# GNSS-proto.net
KiCad netlist of a schematic drawn in EAGLE
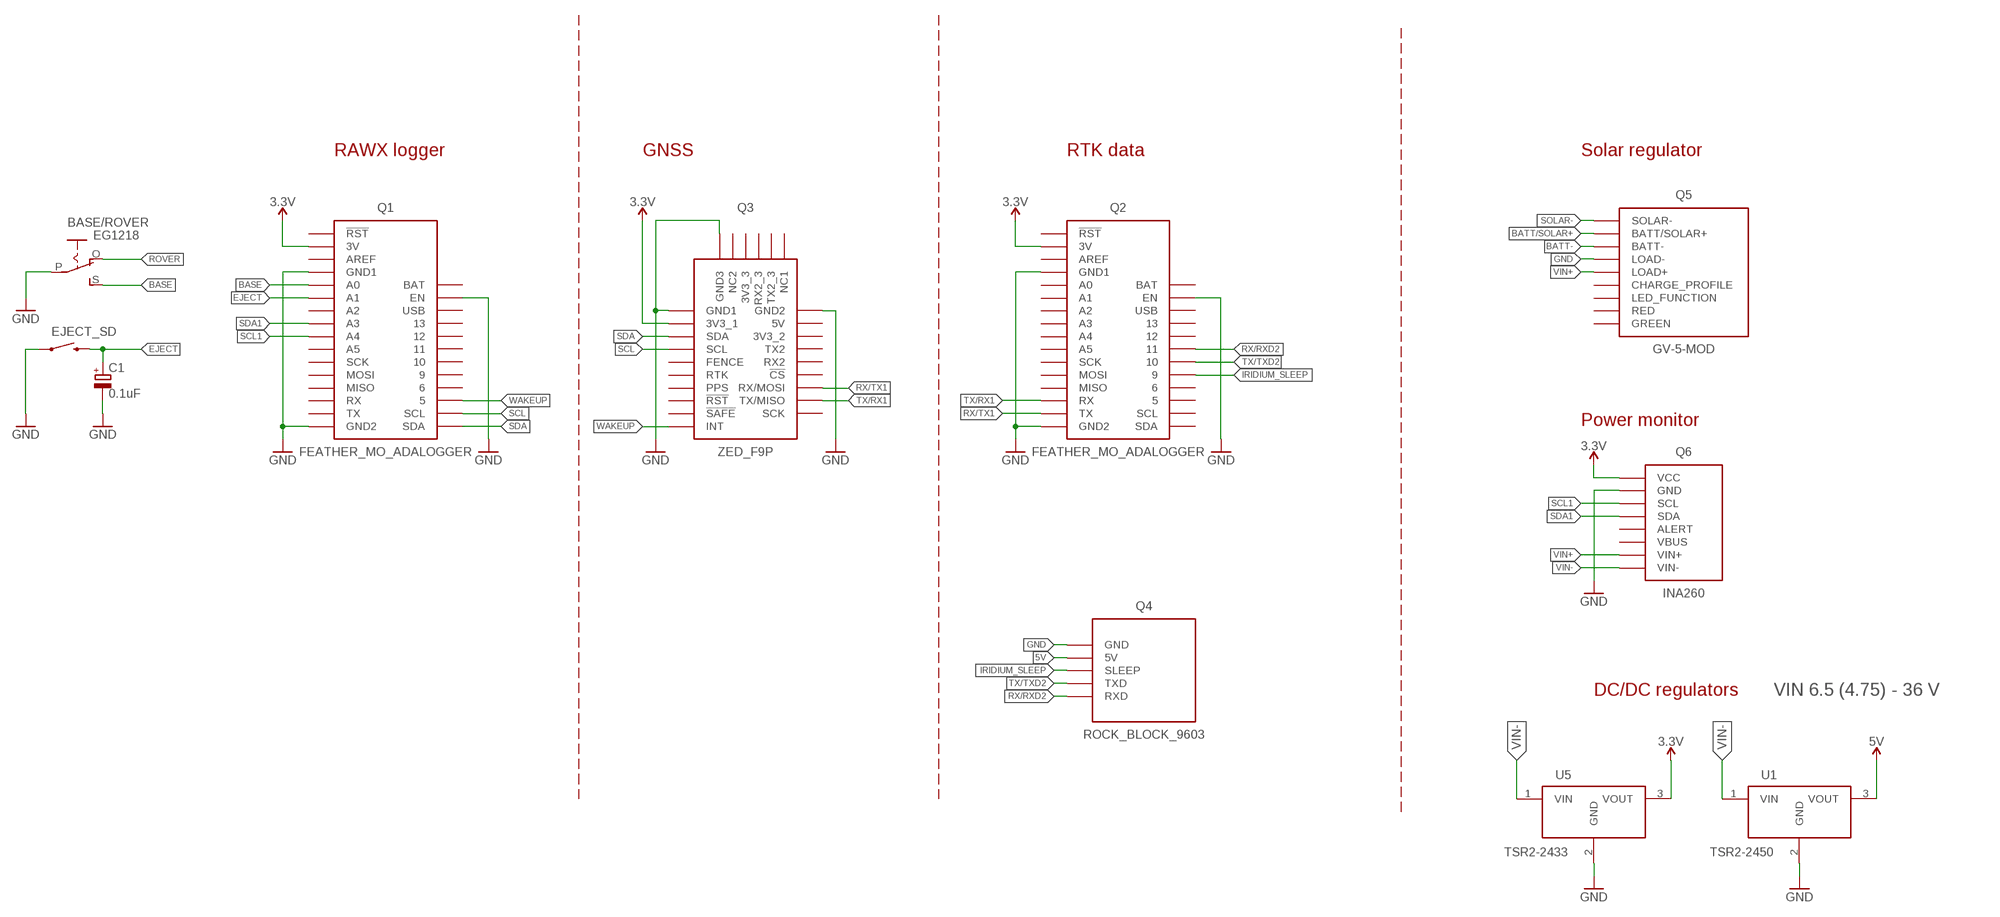
[diagram p0: schematic, sheet 1]

(export (version "E")
  (design (tool "Eeschema 10.0.6"))
  (components
    (comp (ref "BASE/ROVER")
      (value "EG1218")
      (footprint "eagle-import:EG1218")
      (libsource (lib "eagle-import") (part "EG1218S"))
    )
    (comp (ref "C1")
      (value "0.1uF")
      (footprint "eagle-import:E2,5-6E")
      (libsource (lib "eagle-import") (part "CPOL-EUE2,5-6E"))
    )
    (comp (ref "EJECT_SD")
      (value "SWITCH-MOMENTARY-2PTH")
      (footprint "eagle-import:TACTILE-PTH")
      (libsource (lib "eagle-import") (part "SWITCH-MOMENTARY-2PTH"))
    )
    (comp (ref "Q1")
      (value "FEATHER_MO_ADALOGGER")
      (footprint "eagle-import:FEATHER_M0_ADALOGGER")
      (libsource (lib "eagle-import") (part "FEATHER_MO_ADALOGGER"))
    )
    (comp (ref "Q2")
      (value "FEATHER_MO_ADALOGGER")
      (footprint "eagle-import:FEATHER_M0_ADALOGGER")
      (libsource (lib "eagle-import") (part "FEATHER_MO_ADALOGGER"))
    )
    (comp (ref "Q3")
      (value "ZED_F9P")
      (footprint "eagle-import:ZED_F9P")
      (libsource (lib "eagle-import") (part "ZED_F9P"))
    )
    (comp (ref "Q4")
      (value "ROCK_BLOCK_9603")
      (footprint "eagle-import:ROCK_BLOCK_9603")
      (libsource (lib "eagle-import") (part "ROCK_BLOCK_9603"))
    )
    (comp (ref "Q5")
      (value "GV-5-MOD")
      (footprint "eagle-import:GV-5-MOD")
      (libsource (lib "eagle-import") (part "GV-5-MOD"))
    )
    (comp (ref "Q6")
      (value "INA260")
      (footprint "eagle-import:INA260")
      (libsource (lib "eagle-import") (part "INA260"))
    )
    (comp (ref "U1")
      (value "TSR2-2450")
      (footprint "eagle-import:173010535")
      (fields
        (field (name "DIGIKEY_PARTNO") "732-173010535-ND")
        (field (name "MANUFACTURER") "Würth Elektronik")
        (field (name "MPN") "173010535")
        (field (name "CREATED_BY") "PCBLayout.com")
      )
      (libsource (lib "eagle-import") (part "173010535"))
    )
    (comp (ref "U5")
      (value "TSR2-2433")
      (footprint "eagle-import:173010535")
      (fields
        (field (name "DIGIKEY_PARTNO") "732-173010535-ND")
        (field (name "MANUFACTURER") "Würth Elektronik")
        (field (name "MPN") "173010535")
        (field (name "CREATED_BY") "PCBLayout.com")
      )
      (libsource (lib "eagle-import") (part "173010535"))
    )
  )
  (nets
    (net (code "1") (name "3.3V") (class "Default")
      (node (ref "Q1") (pin "3V") (pinfunction "3V_3V") (pintype "bidirectional"))
      (node (ref "Q2") (pin "3V") (pinfunction "3V_3V") (pintype "bidirectional"))
      (node (ref "Q3") (pin "3V3_1") (pinfunction "3V3_1_3V3_1") (pintype "bidirectional"))
      (node (ref "Q6") (pin "VCC") (pinfunction "VCC_VCC") (pintype "bidirectional"))
      (node (ref "U5") (pin "3") (pinfunction "VOUT_3") (pintype "power_in"))
    )
    (net (code "2") (name "5V") (class "Default")
      (node (ref "Q4") (pin "5V") (pinfunction "5V_5V") (pintype "bidirectional"))
      (node (ref "U1") (pin "3") (pinfunction "VOUT_3") (pintype "power_in"))
    )
    (net (code "3") (name "BASE") (class "Default")
      (node (ref "BASE/ROVER") (pin "S") (pinfunction "S_S") (pintype "passive"))
      (node (ref "Q1") (pin "A0") (pinfunction "A0_A0") (pintype "bidirectional"))
    )
    (net (code "4") (name "BATT-") (class "Default")
      (node (ref "Q5") (pin "BATT-1") (pinfunction "BATT-_BATT-1") (pintype "bidirectional"))
      (node (ref "Q5") (pin "BATT-2") (pinfunction "BATT-_BATT-2") (pintype "bidirectional"))
      (node (ref "Q5") (pin "BATT-3") (pinfunction "BATT-_BATT-3") (pintype "bidirectional"))
      (node (ref "Q5") (pin "BATT-4") (pinfunction "BATT-_BATT-4") (pintype "bidirectional"))
    )
    (net (code "5") (name "BATT{slash}SOLAR+") (class "Default")
      (node (ref "Q5") (pin "BATT/SOLAR+1") (pinfunction "BATT/SOLAR+_BATT/SOLAR+1") (pintype "bidirectional"))
      (node (ref "Q5") (pin "BATT/SOLAR+2") (pinfunction "BATT/SOLAR+_BATT/SOLAR+2") (pintype "bidirectional"))
      (node (ref "Q5") (pin "BATT/SOLAR+3") (pinfunction "BATT/SOLAR+_BATT/SOLAR+3") (pintype "bidirectional"))
      (node (ref "Q5") (pin "BATT/SOLAR+4") (pinfunction "BATT/SOLAR+_BATT/SOLAR+4") (pintype "bidirectional"))
    )
    (net (code "6") (name "EJECT") (class "Default")
      (node (ref "C1") (pin "+") (pinfunction "+_+") (pintype "passive"))
      (node (ref "EJECT_SD") (pin "3") (pinfunction "2_3") (pintype "passive"))
      (node (ref "Q1") (pin "A1") (pinfunction "A1_A1") (pintype "bidirectional"))
    )
    (net (code "7") (name "GND") (class "Default")
      (node (ref "BASE/ROVER") (pin "P") (pinfunction "P_P") (pintype "passive"))
      (node (ref "C1") (pin "-") (pinfunction "-_-") (pintype "passive"))
      (node (ref "EJECT_SD") (pin "1") (pinfunction "1_1") (pintype "passive"))
      (node (ref "Q1") (pin "EN") (pinfunction "EN_EN") (pintype "bidirectional"))
      (node (ref "Q1") (pin "GND1") (pinfunction "GND1_GND1") (pintype "bidirectional"))
      (node (ref "Q1") (pin "GND2") (pinfunction "GND2_GND2") (pintype "bidirectional"))
      (node (ref "Q2") (pin "EN") (pinfunction "EN_EN") (pintype "bidirectional"))
      (node (ref "Q2") (pin "GND1") (pinfunction "GND1_GND1") (pintype "bidirectional"))
      (node (ref "Q2") (pin "GND2") (pinfunction "GND2_GND2") (pintype "bidirectional"))
      (node (ref "Q3") (pin "GND1") (pinfunction "GND1_GND1") (pintype "bidirectional"))
      (node (ref "Q3") (pin "GND2") (pinfunction "GND2_GND2") (pintype "bidirectional"))
      (node (ref "Q3") (pin "GND3") (pinfunction "GND3_GND3") (pintype "bidirectional"))
      (node (ref "Q4") (pin "GND1") (pinfunction "GND_GND1") (pintype "bidirectional"))
      (node (ref "Q4") (pin "GND2") (pinfunction "GND_GND2") (pintype "bidirectional"))
      (node (ref "Q5") (pin "LOAD-1") (pinfunction "LOAD-_LOAD-1") (pintype "bidirectional"))
      (node (ref "Q5") (pin "LOAD-2") (pinfunction "LOAD-_LOAD-2") (pintype "bidirectional"))
      (node (ref "Q5") (pin "LOAD-3") (pinfunction "LOAD-_LOAD-3") (pintype "bidirectional"))
      (node (ref "Q5") (pin "LOAD-4") (pinfunction "LOAD-_LOAD-4") (pintype "bidirectional"))
      (node (ref "Q6") (pin "GND") (pinfunction "GND_GND") (pintype "bidirectional"))
      (node (ref "U1") (pin "2") (pinfunction "GND_2") (pintype "power_in"))
      (node (ref "U5") (pin "2") (pinfunction "GND_2") (pintype "power_in"))
    )
    (net (code "8") (name "IRIDIUM_SLEEP") (class "Default")
      (node (ref "Q2") (pin "9") (pinfunction "9_9") (pintype "bidirectional"))
      (node (ref "Q4") (pin "SLEEP") (pinfunction "SLEEP_SLEEP") (pintype "bidirectional"))
    )
    (net (code "9") (name "ROVER") (class "Default")
      (node (ref "BASE/ROVER") (pin "O") (pinfunction "O_O") (pintype "passive"))
    )
    (net (code "10") (name "RX{slash}RXD2") (class "Default")
      (node (ref "Q2") (pin "11") (pinfunction "11_11") (pintype "bidirectional"))
      (node (ref "Q4") (pin "RXD") (pinfunction "RXD_RXD") (pintype "bidirectional"))
    )
    (net (code "11") (name "RX{slash}TX1") (class "Default")
      (node (ref "Q2") (pin "TX") (pinfunction "TX_TX") (pintype "bidirectional"))
      (node (ref "Q3") (pin "RX/MOSI") (pinfunction "RX/MOSI_RX/MOSI") (pintype "bidirectional"))
    )
    (net (code "12") (name "SCL") (class "Default")
      (node (ref "Q1") (pin "SCL") (pinfunction "SCL_SCL") (pintype "bidirectional"))
      (node (ref "Q3") (pin "SCL") (pinfunction "SCL_SCL") (pintype "bidirectional"))
    )
    (net (code "13") (name "SCL1") (class "Default")
      (node (ref "Q1") (pin "A4") (pinfunction "A4_A4") (pintype "bidirectional"))
      (node (ref "Q6") (pin "SCL") (pinfunction "SCL_SCL") (pintype "bidirectional"))
    )
    (net (code "14") (name "SDA") (class "Default")
      (node (ref "Q1") (pin "SDA") (pinfunction "SDA_SDA") (pintype "bidirectional"))
      (node (ref "Q3") (pin "SDA") (pinfunction "SDA_SDA") (pintype "bidirectional"))
    )
    (net (code "15") (name "SDA1") (class "Default")
      (node (ref "Q1") (pin "A3") (pinfunction "A3_A3") (pintype "bidirectional"))
      (node (ref "Q6") (pin "SDA") (pinfunction "SDA_SDA") (pintype "bidirectional"))
    )
    (net (code "16") (name "SOLAR-") (class "Default")
      (node (ref "Q5") (pin "SOLAR-1") (pinfunction "SOLAR-_SOLAR-1") (pintype "bidirectional"))
      (node (ref "Q5") (pin "SOLAR-2") (pinfunction "SOLAR-_SOLAR-2") (pintype "bidirectional"))
      (node (ref "Q5") (pin "SOLAR-3") (pinfunction "SOLAR-_SOLAR-3") (pintype "bidirectional"))
      (node (ref "Q5") (pin "SOLAR-4") (pinfunction "SOLAR-_SOLAR-4") (pintype "bidirectional"))
    )
    (net (code "17") (name "TX{slash}RX1") (class "Default")
      (node (ref "Q2") (pin "RX") (pinfunction "RX_RX") (pintype "bidirectional"))
      (node (ref "Q3") (pin "TX/MISO") (pinfunction "TX/MISO_TX/MISO") (pintype "bidirectional"))
    )
    (net (code "18") (name "TX{slash}TXD2") (class "Default")
      (node (ref "Q2") (pin "10") (pinfunction "10_10") (pintype "bidirectional"))
      (node (ref "Q4") (pin "TXD") (pinfunction "TXD_TXD") (pintype "bidirectional"))
    )
    (net (code "19") (name "VIN+") (class "Default")
      (node (ref "Q5") (pin "LOAD+1") (pinfunction "LOAD+_LOAD+1") (pintype "bidirectional"))
      (node (ref "Q5") (pin "LOAD+2") (pinfunction "LOAD+_LOAD+2") (pintype "bidirectional"))
      (node (ref "Q5") (pin "LOAD+3") (pinfunction "LOAD+_LOAD+3") (pintype "bidirectional"))
      (node (ref "Q5") (pin "LOAD+4") (pinfunction "LOAD+_LOAD+4") (pintype "bidirectional"))
      (node (ref "Q6") (pin "VIN+1") (pinfunction "VIN+_VIN+1") (pintype "bidirectional"))
      (node (ref "Q6") (pin "VIN+2") (pinfunction "VIN+_VIN+2") (pintype "bidirectional"))
    )
    (net (code "20") (name "VIN-") (class "Default")
      (node (ref "Q6") (pin "VIN-1") (pinfunction "VIN-_VIN-1") (pintype "bidirectional"))
      (node (ref "Q6") (pin "VIN-2") (pinfunction "VIN-_VIN-2") (pintype "bidirectional"))
      (node (ref "U1") (pin "1") (pinfunction "VIN_1") (pintype "power_in"))
      (node (ref "U5") (pin "1") (pinfunction "VIN_1") (pintype "power_in"))
    )
    (net (code "21") (name "WAKEUP") (class "Default")
      (node (ref "Q1") (pin "5") (pinfunction "5_5") (pintype "bidirectional"))
      (node (ref "Q3") (pin "INT") (pinfunction "INT_INT") (pintype "bidirectional"))
    )
    (net (code "22") (name "unconnected-(Q1-Pad6)") (class "Default")
      (node (ref "Q1") (pin "6") (pinfunction "6_6") (pintype "bidirectional"))
    )
    (net (code "23") (name "unconnected-(Q1-Pad9)") (class "Default")
      (node (ref "Q1") (pin "9") (pinfunction "9_9") (pintype "bidirectional"))
    )
    (net (code "24") (name "unconnected-(Q1-Pad10)") (class "Default")
      (node (ref "Q1") (pin "10") (pinfunction "10_10") (pintype "bidirectional"))
    )
    (net (code "25") (name "unconnected-(Q1-Pad11)") (class "Default")
      (node (ref "Q1") (pin "11") (pinfunction "11_11") (pintype "bidirectional"))
    )
    (net (code "26") (name "unconnected-(Q1-Pad12)") (class "Default")
      (node (ref "Q1") (pin "12") (pinfunction "12_12") (pintype "bidirectional"))
    )
    (net (code "27") (name "unconnected-(Q1-Pad13)") (class "Default")
      (node (ref "Q1") (pin "13") (pinfunction "13_13") (pintype "bidirectional"))
    )
    (net (code "28") (name "unconnected-(Q1-PadA2)") (class "Default")
      (node (ref "Q1") (pin "A2") (pinfunction "A2_A2") (pintype "bidirectional"))
    )
    (net (code "29") (name "unconnected-(Q1-PadA5)") (class "Default")
      (node (ref "Q1") (pin "A5") (pinfunction "A5_A5") (pintype "bidirectional"))
    )
    (net (code "30") (name "unconnected-(Q1-PadAREF)") (class "Default")
      (node (ref "Q1") (pin "AREF") (pinfunction "AREF_AREF") (pintype "bidirectional"))
    )
    (net (code "31") (name "unconnected-(Q1-PadBAT)") (class "Default")
      (node (ref "Q1") (pin "BAT") (pinfunction "BAT_BAT") (pintype "bidirectional"))
    )
    (net (code "32") (name "unconnected-(Q1-PadMISO)") (class "Default")
      (node (ref "Q1") (pin "MISO") (pinfunction "MISO_MISO") (pintype "bidirectional"))
    )
    (net (code "33") (name "unconnected-(Q1-PadMOSI)") (class "Default")
      (node (ref "Q1") (pin "MOSI") (pinfunction "MOSI_MOSI") (pintype "bidirectional"))
    )
    (net (code "34") (name "unconnected-(Q1-PadRX)") (class "Default")
      (node (ref "Q1") (pin "RX") (pinfunction "RX_RX") (pintype "bidirectional"))
    )
    (net (code "35") (name "unconnected-(Q1-PadSCK)") (class "Default")
      (node (ref "Q1") (pin "SCK") (pinfunction "SCK_SCK") (pintype "bidirectional"))
    )
    (net (code "36") (name "unconnected-(Q1-PadTX)") (class "Default")
      (node (ref "Q1") (pin "TX") (pinfunction "TX_TX") (pintype "bidirectional"))
    )
    (net (code "37") (name "unconnected-(Q1-PadUSB)") (class "Default")
      (node (ref "Q1") (pin "USB") (pinfunction "USB_USB") (pintype "bidirectional"))
    )
    (net (code "38") (name "unconnected-(Q1-~{RST}-Pad!RST)") (class "Default")
      (node (ref "Q1") (pin "!RST") (pinfunction "~{RST}_!RST") (pintype "bidirectional"))
    )
    (net (code "39") (name "unconnected-(Q2-Pad5)") (class "Default")
      (node (ref "Q2") (pin "5") (pinfunction "5_5") (pintype "bidirectional"))
    )
    (net (code "40") (name "unconnected-(Q2-Pad6)") (class "Default")
      (node (ref "Q2") (pin "6") (pinfunction "6_6") (pintype "bidirectional"))
    )
    (net (code "41") (name "unconnected-(Q2-Pad12)") (class "Default")
      (node (ref "Q2") (pin "12") (pinfunction "12_12") (pintype "bidirectional"))
    )
    (net (code "42") (name "unconnected-(Q2-Pad13)") (class "Default")
      (node (ref "Q2") (pin "13") (pinfunction "13_13") (pintype "bidirectional"))
    )
    (net (code "43") (name "unconnected-(Q2-PadA0)") (class "Default")
      (node (ref "Q2") (pin "A0") (pinfunction "A0_A0") (pintype "bidirectional"))
    )
    (net (code "44") (name "unconnected-(Q2-PadA1)") (class "Default")
      (node (ref "Q2") (pin "A1") (pinfunction "A1_A1") (pintype "bidirectional"))
    )
    (net (code "45") (name "unconnected-(Q2-PadA2)") (class "Default")
      (node (ref "Q2") (pin "A2") (pinfunction "A2_A2") (pintype "bidirectional"))
    )
    (net (code "46") (name "unconnected-(Q2-PadA3)") (class "Default")
      (node (ref "Q2") (pin "A3") (pinfunction "A3_A3") (pintype "bidirectional"))
    )
    (net (code "47") (name "unconnected-(Q2-PadA4)") (class "Default")
      (node (ref "Q2") (pin "A4") (pinfunction "A4_A4") (pintype "bidirectional"))
    )
    (net (code "48") (name "unconnected-(Q2-PadA5)") (class "Default")
      (node (ref "Q2") (pin "A5") (pinfunction "A5_A5") (pintype "bidirectional"))
    )
    (net (code "49") (name "unconnected-(Q2-PadAREF)") (class "Default")
      (node (ref "Q2") (pin "AREF") (pinfunction "AREF_AREF") (pintype "bidirectional"))
    )
    (net (code "50") (name "unconnected-(Q2-PadBAT)") (class "Default")
      (node (ref "Q2") (pin "BAT") (pinfunction "BAT_BAT") (pintype "bidirectional"))
    )
    (net (code "51") (name "unconnected-(Q2-PadMISO)") (class "Default")
      (node (ref "Q2") (pin "MISO") (pinfunction "MISO_MISO") (pintype "bidirectional"))
    )
    (net (code "52") (name "unconnected-(Q2-PadMOSI)") (class "Default")
      (node (ref "Q2") (pin "MOSI") (pinfunction "MOSI_MOSI") (pintype "bidirectional"))
    )
    (net (code "53") (name "unconnected-(Q2-PadSCK)") (class "Default")
      (node (ref "Q2") (pin "SCK") (pinfunction "SCK_SCK") (pintype "bidirectional"))
    )
    (net (code "54") (name "unconnected-(Q2-PadSCL)") (class "Default")
      (node (ref "Q2") (pin "SCL") (pinfunction "SCL_SCL") (pintype "bidirectional"))
    )
    (net (code "55") (name "unconnected-(Q2-PadSDA)") (class "Default")
      (node (ref "Q2") (pin "SDA") (pinfunction "SDA_SDA") (pintype "bidirectional"))
    )
    (net (code "56") (name "unconnected-(Q2-PadUSB)") (class "Default")
      (node (ref "Q2") (pin "USB") (pinfunction "USB_USB") (pintype "bidirectional"))
    )
    (net (code "57") (name "unconnected-(Q2-~{RST}-Pad!RST)") (class "Default")
      (node (ref "Q2") (pin "!RST") (pinfunction "~{RST}_!RST") (pintype "bidirectional"))
    )
    (net (code "58") (name "unconnected-(Q3-NC1-PadNC_1)") (class "Default")
      (node (ref "Q3") (pin "NC_1") (pinfunction "NC1_NC_1") (pintype "bidirectional"))
    )
    (net (code "59") (name "unconnected-(Q3-NC2-PadNC_2)") (class "Default")
      (node (ref "Q3") (pin "NC_2") (pinfunction "NC2_NC_2") (pintype "bidirectional"))
    )
    (net (code "60") (name "unconnected-(Q3-Pad3V3_2)") (class "Default")
      (node (ref "Q3") (pin "3V3_2") (pinfunction "3V3_2_3V3_2") (pintype "bidirectional"))
    )
    (net (code "61") (name "unconnected-(Q3-Pad3V3_3)") (class "Default")
      (node (ref "Q3") (pin "3V3_3") (pinfunction "3V3_3_3V3_3") (pintype "bidirectional"))
    )
    (net (code "62") (name "unconnected-(Q3-Pad5V)") (class "Default")
      (node (ref "Q3") (pin "5V") (pinfunction "5V_5V") (pintype "bidirectional"))
    )
    (net (code "63") (name "unconnected-(Q3-PadFENCE)") (class "Default")
      (node (ref "Q3") (pin "FENCE") (pinfunction "FENCE_FENCE") (pintype "bidirectional"))
    )
    (net (code "64") (name "unconnected-(Q3-PadPPS)") (class "Default")
      (node (ref "Q3") (pin "PPS") (pinfunction "PPS_PPS") (pintype "bidirectional"))
    )
    (net (code "65") (name "unconnected-(Q3-PadRTK)") (class "Default")
      (node (ref "Q3") (pin "RTK") (pinfunction "RTK_RTK") (pintype "bidirectional"))
    )
    (net (code "66") (name "unconnected-(Q3-PadRX2)") (class "Default")
      (node (ref "Q3") (pin "RX2") (pinfunction "RX2_RX2") (pintype "bidirectional"))
    )
    (net (code "67") (name "unconnected-(Q3-PadRX2_3)") (class "Default")
      (node (ref "Q3") (pin "RX2_3") (pinfunction "RX2_3_RX2_3") (pintype "bidirectional"))
    )
    (net (code "68") (name "unconnected-(Q3-PadSCK)") (class "Default")
      (node (ref "Q3") (pin "SCK") (pinfunction "SCK_SCK") (pintype "bidirectional"))
    )
    (net (code "69") (name "unconnected-(Q3-PadTX2)") (class "Default")
      (node (ref "Q3") (pin "TX2") (pinfunction "TX2_TX2") (pintype "bidirectional"))
    )
    (net (code "70") (name "unconnected-(Q3-PadTX2_3)") (class "Default")
      (node (ref "Q3") (pin "TX2_3") (pinfunction "TX2_3_TX2_3") (pintype "bidirectional"))
    )
    (net (code "71") (name "unconnected-(Q3-~{CS}-Pad!CS)") (class "Default")
      (node (ref "Q3") (pin "!CS") (pinfunction "~{CS}_!CS") (pintype "bidirectional"))
    )
    (net (code "72") (name "unconnected-(Q3-~{RST}-Pad!RST)") (class "Default")
      (node (ref "Q3") (pin "!RST") (pinfunction "~{RST}_!RST") (pintype "bidirectional"))
    )
    (net (code "73") (name "unconnected-(Q3-~{SAFE}-Pad!SAFE)") (class "Default")
      (node (ref "Q3") (pin "!SAFE") (pinfunction "~{SAFE}_!SAFE") (pintype "bidirectional"))
    )
    (net (code "74") (name "unconnected-(Q5-CHARGE_PROFILE-PadCHG_PROFILE)") (class "Default")
      (node (ref "Q5") (pin "CHG_PROFILE") (pinfunction "CHARGE_PROFILE_CHG_PROFILE") (pintype "bidirectional"))
    )
    (net (code "75") (name "unconnected-(Q5-PadGREEN)") (class "Default")
      (node (ref "Q5") (pin "GREEN") (pinfunction "GREEN_GREEN") (pintype "bidirectional"))
    )
    (net (code "76") (name "unconnected-(Q5-PadLED_FUNCTION)") (class "Default")
      (node (ref "Q5") (pin "LED_FUNCTION") (pinfunction "LED_FUNCTION_LED_FUNCTION") (pintype "bidirectional"))
    )
    (net (code "77") (name "unconnected-(Q5-PadRED)") (class "Default")
      (node (ref "Q5") (pin "RED") (pinfunction "RED_RED") (pintype "bidirectional"))
    )
    (net (code "78") (name "unconnected-(Q6-PadALERT)") (class "Default")
      (node (ref "Q6") (pin "ALERT") (pinfunction "ALERT_ALERT") (pintype "bidirectional"))
    )
    (net (code "79") (name "unconnected-(Q6-PadVBUS)") (class "Default")
      (node (ref "Q6") (pin "VBUS") (pinfunction "VBUS_VBUS") (pintype "bidirectional"))
    )
  )
)
